# mitosis.net
KiCad netlist of a schematic drawn in Altium Designer
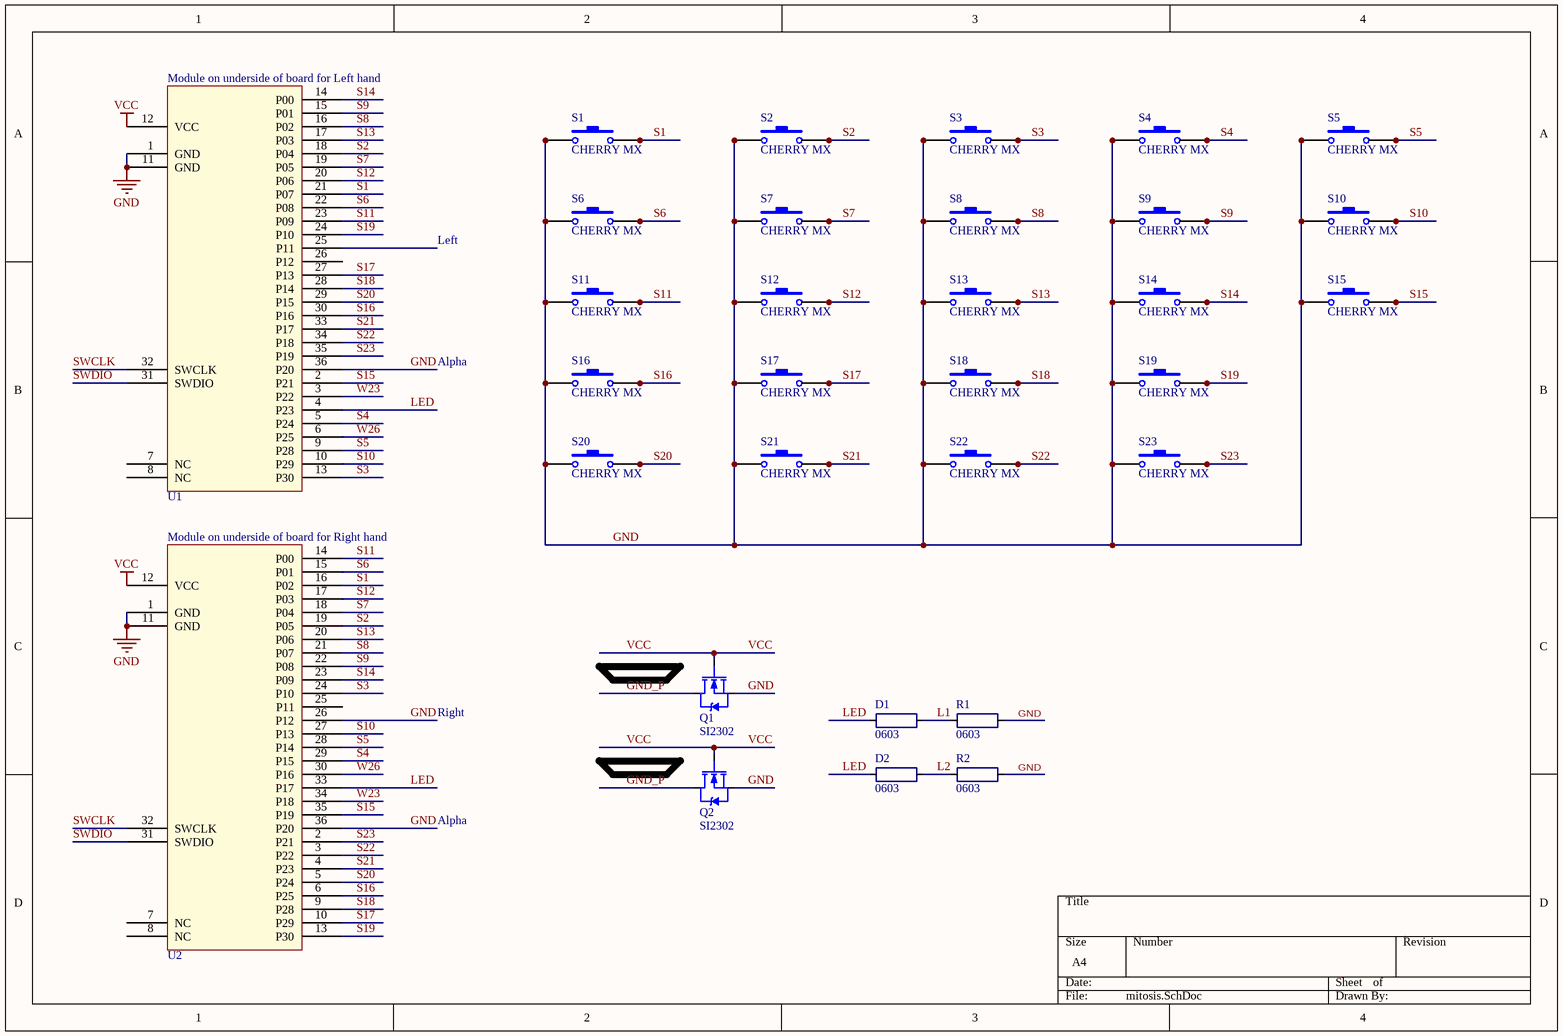
[diagram p0: mitosis.SchDoc]

(export (version "E")
  (design (tool "Eeschema 10.0.6"))
  (components
    (comp (ref "D1") (value "0603") (footprint "RESC2012X06N") (libsource (lib "SK") (part "0603")))
    (comp (ref "D2") (value "0603") (footprint "RESC2012X06N") (libsource (lib "SK") (part "0603")))
    (comp (ref "Q1")
      (value "SI2302")
      (footprint "SOT-23")
      (description "N-Channel Logic MOSFET")
      (fields (field (name "PUBLISHER") "Altium Limited"))
      (libsource (lib "SK") (part "SI2302"))
    )
    (comp (ref "Q2")
      (value "SI2302")
      (footprint "SOT-23")
      (description "N-Channel Logic MOSFET")
      (fields (field (name "PUBLISHER") "Altium Limited"))
      (libsource (lib "SK") (part "SI2302"))
    )
    (comp (ref "R1") (value "0603") (footprint "RESC2012X06N") (libsource (lib "SK") (part "0603")))
    (comp (ref "R2") (value "0603") (footprint "RESC2012X06N") (libsource (lib "SK") (part "0603")))
    (comp (ref "S1")
      (value "CHERRY MX")
      (footprint "cherry")
      (description "Switch")
      (fields (field (name "PUBLISHER") "Altium Limited"))
      (libsource (lib "SK") (part "CHERRY MX"))
    )
    (comp (ref "S2")
      (value "CHERRY MX")
      (footprint "cherry")
      (description "Switch")
      (fields (field (name "PUBLISHER") "Altium Limited"))
      (libsource (lib "SK") (part "CHERRY MX"))
    )
    (comp (ref "S3")
      (value "CHERRY MX")
      (footprint "cherry")
      (description "Switch")
      (fields (field (name "PUBLISHER") "Altium Limited"))
      (libsource (lib "SK") (part "CHERRY MX"))
    )
    (comp (ref "S4")
      (value "CHERRY MX")
      (footprint "cherry")
      (description "Switch")
      (fields (field (name "PUBLISHER") "Altium Limited"))
      (libsource (lib "SK") (part "CHERRY MX"))
    )
    (comp (ref "S5")
      (value "CHERRY MX")
      (footprint "cherry")
      (description "Switch")
      (fields (field (name "PUBLISHER") "Altium Limited"))
      (libsource (lib "SK") (part "CHERRY MX"))
    )
    (comp (ref "S6")
      (value "CHERRY MX")
      (footprint "cherry")
      (description "Switch")
      (fields (field (name "PUBLISHER") "Altium Limited"))
      (libsource (lib "SK") (part "CHERRY MX"))
    )
    (comp (ref "S7")
      (value "CHERRY MX")
      (footprint "cherry")
      (description "Switch")
      (fields (field (name "PUBLISHER") "Altium Limited"))
      (libsource (lib "SK") (part "CHERRY MX"))
    )
    (comp (ref "S8")
      (value "CHERRY MX")
      (footprint "cherry")
      (description "Switch")
      (fields (field (name "PUBLISHER") "Altium Limited"))
      (libsource (lib "SK") (part "CHERRY MX"))
    )
    (comp (ref "S9")
      (value "CHERRY MX")
      (footprint "cherry")
      (description "Switch")
      (fields (field (name "PUBLISHER") "Altium Limited"))
      (libsource (lib "SK") (part "CHERRY MX"))
    )
    (comp (ref "S10")
      (value "CHERRY MX")
      (footprint "cherry")
      (description "Switch")
      (fields (field (name "PUBLISHER") "Altium Limited"))
      (libsource (lib "SK") (part "CHERRY MX"))
    )
    (comp (ref "S11")
      (value "CHERRY MX")
      (footprint "cherry")
      (description "Switch")
      (fields (field (name "PUBLISHER") "Altium Limited"))
      (libsource (lib "SK") (part "CHERRY MX"))
    )
    (comp (ref "S12")
      (value "CHERRY MX")
      (footprint "cherry")
      (description "Switch")
      (fields (field (name "PUBLISHER") "Altium Limited"))
      (libsource (lib "SK") (part "CHERRY MX"))
    )
    (comp (ref "S13")
      (value "CHERRY MX")
      (footprint "cherry")
      (description "Switch")
      (fields (field (name "PUBLISHER") "Altium Limited"))
      (libsource (lib "SK") (part "CHERRY MX"))
    )
    (comp (ref "S14")
      (value "CHERRY MX")
      (footprint "cherry")
      (description "Switch")
      (fields (field (name "PUBLISHER") "Altium Limited"))
      (libsource (lib "SK") (part "CHERRY MX"))
    )
    (comp (ref "S15")
      (value "CHERRY MX")
      (footprint "cherry")
      (description "Switch")
      (fields (field (name "PUBLISHER") "Altium Limited"))
      (libsource (lib "SK") (part "CHERRY MX"))
    )
    (comp (ref "S16")
      (value "CHERRY MX")
      (footprint "cherry")
      (description "Switch")
      (fields (field (name "PUBLISHER") "Altium Limited"))
      (libsource (lib "SK") (part "CHERRY MX"))
    )
    (comp (ref "S17")
      (value "CHERRY MX")
      (footprint "cherry")
      (description "Switch")
      (fields (field (name "PUBLISHER") "Altium Limited"))
      (libsource (lib "SK") (part "CHERRY MX"))
    )
    (comp (ref "S18")
      (value "CHERRY MX")
      (footprint "cherry")
      (description "Switch")
      (fields (field (name "PUBLISHER") "Altium Limited"))
      (libsource (lib "SK") (part "CHERRY MX"))
    )
    (comp (ref "S19")
      (value "CHERRY MX")
      (footprint "cherry")
      (description "Switch")
      (fields (field (name "PUBLISHER") "Altium Limited"))
      (libsource (lib "SK") (part "CHERRY MX"))
    )
    (comp (ref "S20")
      (value "CHERRY MX")
      (footprint "cherry")
      (description "Switch")
      (fields (field (name "PUBLISHER") "Altium Limited"))
      (libsource (lib "SK") (part "CHERRY MX"))
    )
    (comp (ref "S21")
      (value "CHERRY MX")
      (footprint "cherry")
      (description "Switch")
      (fields (field (name "PUBLISHER") "Altium Limited"))
      (libsource (lib "SK") (part "CHERRY MX"))
    )
    (comp (ref "S22")
      (value "CHERRY MX")
      (footprint "cherry")
      (description "Switch")
      (fields (field (name "PUBLISHER") "Altium Limited"))
      (libsource (lib "SK") (part "CHERRY MX"))
    )
    (comp (ref "S23")
      (value "CHERRY MX")
      (footprint "cherry")
      (description "Switch")
      (fields (field (name "PUBLISHER") "Altium Limited"))
      (libsource (lib "SK") (part "CHERRY MX"))
    )
    (comp (ref "U1")
      (value "Core51822 (B)")
      (footprint "Core51822 (B)")
      (description "NRF51822 (B)")
      (libsource (lib "SK") (part "Core51822 (B)"))
    )
    (comp (ref "U2")
      (value "Core51822 (B)")
      (footprint "Core51822 (B)")
      (description "NRF51822 (B)")
      (libsource (lib "SK") (part "Core51822 (B)"))
    )
  )
  (nets
    (net (code "1") (name "/GND_P") (class "Default")
      (node (ref "Q1") (pin "3") (pinfunction "D_3") (pintype "passive"))
      (node (ref "Q2") (pin "3") (pinfunction "D_3") (pintype "passive"))
    )
    (net (code "2") (name "/L1") (class "Default")
      (node (ref "D1") (pin "1") (pinfunction "1_1") (pintype "passive"))
      (node (ref "R1") (pin "2") (pinfunction "2_2") (pintype "passive"))
    )
    (net (code "3") (name "/L2") (class "Default")
      (node (ref "D2") (pin "1") (pinfunction "1_1") (pintype "passive"))
      (node (ref "R2") (pin "2") (pinfunction "2_2") (pintype "passive"))
    )
    (net (code "4") (name "/LED") (class "Default")
      (node (ref "D1") (pin "2") (pinfunction "2_2") (pintype "passive"))
      (node (ref "D2") (pin "2") (pinfunction "2_2") (pintype "passive"))
      (node (ref "U1") (pin "4") (pinfunction "P23_4") (pintype "passive"))
      (node (ref "U2") (pin "33") (pinfunction "P17_33") (pintype "passive"))
    )
    (net (code "5") (name "/S1") (class "Default")
      (node (ref "S1") (pin "10") (pinfunction "10_10") (pintype "passive"))
      (node (ref "S1") (pin "12") (pinfunction "12_12") (pintype "passive"))
      (node (ref "S1") (pin "2") (pinfunction "2_2") (pintype "passive"))
      (node (ref "S1") (pin "4") (pinfunction "4_4") (pintype "passive"))
      (node (ref "S1") (pin "6") (pinfunction "6_6") (pintype "passive"))
      (node (ref "S1") (pin "8") (pinfunction "8_8") (pintype "passive"))
      (node (ref "U1") (pin "21") (pinfunction "P07_21") (pintype "passive"))
      (node (ref "U2") (pin "16") (pinfunction "P02_16") (pintype "passive"))
    )
    (net (code "6") (name "/S2") (class "Default")
      (node (ref "S2") (pin "10") (pinfunction "10_10") (pintype "passive"))
      (node (ref "S2") (pin "12") (pinfunction "12_12") (pintype "passive"))
      (node (ref "S2") (pin "2") (pinfunction "2_2") (pintype "passive"))
      (node (ref "S2") (pin "4") (pinfunction "4_4") (pintype "passive"))
      (node (ref "S2") (pin "6") (pinfunction "6_6") (pintype "passive"))
      (node (ref "S2") (pin "8") (pinfunction "8_8") (pintype "passive"))
      (node (ref "U1") (pin "18") (pinfunction "P04_18") (pintype "passive"))
      (node (ref "U2") (pin "19") (pinfunction "P05_19") (pintype "passive"))
    )
    (net (code "7") (name "/S3") (class "Default")
      (node (ref "S3") (pin "10") (pinfunction "10_10") (pintype "passive"))
      (node (ref "S3") (pin "12") (pinfunction "12_12") (pintype "passive"))
      (node (ref "S3") (pin "2") (pinfunction "2_2") (pintype "passive"))
      (node (ref "S3") (pin "4") (pinfunction "4_4") (pintype "passive"))
      (node (ref "S3") (pin "6") (pinfunction "6_6") (pintype "passive"))
      (node (ref "S3") (pin "8") (pinfunction "8_8") (pintype "passive"))
      (node (ref "U1") (pin "13") (pinfunction "P30_13") (pintype "passive"))
      (node (ref "U2") (pin "24") (pinfunction "P10_24") (pintype "passive"))
    )
    (net (code "8") (name "/S4") (class "Default")
      (node (ref "S4") (pin "10") (pinfunction "10_10") (pintype "passive"))
      (node (ref "S4") (pin "12") (pinfunction "12_12") (pintype "passive"))
      (node (ref "S4") (pin "2") (pinfunction "2_2") (pintype "passive"))
      (node (ref "S4") (pin "4") (pinfunction "4_4") (pintype "passive"))
      (node (ref "S4") (pin "6") (pinfunction "6_6") (pintype "passive"))
      (node (ref "S4") (pin "8") (pinfunction "8_8") (pintype "passive"))
      (node (ref "U1") (pin "5") (pinfunction "P24_5") (pintype "passive"))
      (node (ref "U2") (pin "29") (pinfunction "P15_29") (pintype "passive"))
    )
    (net (code "9") (name "/S5") (class "Default")
      (node (ref "S5") (pin "10") (pinfunction "10_10") (pintype "passive"))
      (node (ref "S5") (pin "12") (pinfunction "12_12") (pintype "passive"))
      (node (ref "S5") (pin "2") (pinfunction "2_2") (pintype "passive"))
      (node (ref "S5") (pin "4") (pinfunction "4_4") (pintype "passive"))
      (node (ref "S5") (pin "6") (pinfunction "6_6") (pintype "passive"))
      (node (ref "S5") (pin "8") (pinfunction "8_8") (pintype "passive"))
      (node (ref "U1") (pin "9") (pinfunction "P28_9") (pintype "passive"))
      (node (ref "U2") (pin "28") (pinfunction "P14_28") (pintype "passive"))
    )
    (net (code "10") (name "/S6") (class "Default")
      (node (ref "S6") (pin "10") (pinfunction "10_10") (pintype "passive"))
      (node (ref "S6") (pin "12") (pinfunction "12_12") (pintype "passive"))
      (node (ref "S6") (pin "2") (pinfunction "2_2") (pintype "passive"))
      (node (ref "S6") (pin "4") (pinfunction "4_4") (pintype "passive"))
      (node (ref "S6") (pin "6") (pinfunction "6_6") (pintype "passive"))
      (node (ref "S6") (pin "8") (pinfunction "8_8") (pintype "passive"))
      (node (ref "U1") (pin "22") (pinfunction "P08_22") (pintype "passive"))
      (node (ref "U2") (pin "15") (pinfunction "P01_15") (pintype "passive"))
    )
    (net (code "11") (name "/S7") (class "Default")
      (node (ref "S7") (pin "10") (pinfunction "10_10") (pintype "passive"))
      (node (ref "S7") (pin "12") (pinfunction "12_12") (pintype "passive"))
      (node (ref "S7") (pin "2") (pinfunction "2_2") (pintype "passive"))
      (node (ref "S7") (pin "4") (pinfunction "4_4") (pintype "passive"))
      (node (ref "S7") (pin "6") (pinfunction "6_6") (pintype "passive"))
      (node (ref "S7") (pin "8") (pinfunction "8_8") (pintype "passive"))
      (node (ref "U1") (pin "19") (pinfunction "P05_19") (pintype "passive"))
      (node (ref "U2") (pin "18") (pinfunction "P04_18") (pintype "passive"))
    )
    (net (code "12") (name "/S8") (class "Default")
      (node (ref "S8") (pin "10") (pinfunction "10_10") (pintype "passive"))
      (node (ref "S8") (pin "12") (pinfunction "12_12") (pintype "passive"))
      (node (ref "S8") (pin "2") (pinfunction "2_2") (pintype "passive"))
      (node (ref "S8") (pin "4") (pinfunction "4_4") (pintype "passive"))
      (node (ref "S8") (pin "6") (pinfunction "6_6") (pintype "passive"))
      (node (ref "S8") (pin "8") (pinfunction "8_8") (pintype "passive"))
      (node (ref "U1") (pin "16") (pinfunction "P02_16") (pintype "passive"))
      (node (ref "U2") (pin "21") (pinfunction "P07_21") (pintype "passive"))
    )
    (net (code "13") (name "/S9") (class "Default")
      (node (ref "S9") (pin "10") (pinfunction "10_10") (pintype "passive"))
      (node (ref "S9") (pin "12") (pinfunction "12_12") (pintype "passive"))
      (node (ref "S9") (pin "2") (pinfunction "2_2") (pintype "passive"))
      (node (ref "S9") (pin "4") (pinfunction "4_4") (pintype "passive"))
      (node (ref "S9") (pin "6") (pinfunction "6_6") (pintype "passive"))
      (node (ref "S9") (pin "8") (pinfunction "8_8") (pintype "passive"))
      (node (ref "U1") (pin "15") (pinfunction "P01_15") (pintype "passive"))
      (node (ref "U2") (pin "22") (pinfunction "P08_22") (pintype "passive"))
    )
    (net (code "14") (name "/S10") (class "Default")
      (node (ref "S10") (pin "10") (pinfunction "10_10") (pintype "passive"))
      (node (ref "S10") (pin "12") (pinfunction "12_12") (pintype "passive"))
      (node (ref "S10") (pin "2") (pinfunction "2_2") (pintype "passive"))
      (node (ref "S10") (pin "4") (pinfunction "4_4") (pintype "passive"))
      (node (ref "S10") (pin "6") (pinfunction "6_6") (pintype "passive"))
      (node (ref "S10") (pin "8") (pinfunction "8_8") (pintype "passive"))
      (node (ref "U1") (pin "10") (pinfunction "P29_10") (pintype "passive"))
      (node (ref "U2") (pin "27") (pinfunction "P13_27") (pintype "passive"))
    )
    (net (code "15") (name "/S11") (class "Default")
      (node (ref "S11") (pin "10") (pinfunction "10_10") (pintype "passive"))
      (node (ref "S11") (pin "12") (pinfunction "12_12") (pintype "passive"))
      (node (ref "S11") (pin "2") (pinfunction "2_2") (pintype "passive"))
      (node (ref "S11") (pin "4") (pinfunction "4_4") (pintype "passive"))
      (node (ref "S11") (pin "6") (pinfunction "6_6") (pintype "passive"))
      (node (ref "S11") (pin "8") (pinfunction "8_8") (pintype "passive"))
      (node (ref "U1") (pin "23") (pinfunction "P09_23") (pintype "passive"))
      (node (ref "U2") (pin "14") (pinfunction "P00_14") (pintype "passive"))
    )
    (net (code "16") (name "/S12") (class "Default")
      (node (ref "S12") (pin "10") (pinfunction "10_10") (pintype "passive"))
      (node (ref "S12") (pin "12") (pinfunction "12_12") (pintype "passive"))
      (node (ref "S12") (pin "2") (pinfunction "2_2") (pintype "passive"))
      (node (ref "S12") (pin "4") (pinfunction "4_4") (pintype "passive"))
      (node (ref "S12") (pin "6") (pinfunction "6_6") (pintype "passive"))
      (node (ref "S12") (pin "8") (pinfunction "8_8") (pintype "passive"))
      (node (ref "U1") (pin "20") (pinfunction "P06_20") (pintype "passive"))
      (node (ref "U2") (pin "17") (pinfunction "P03_17") (pintype "passive"))
    )
    (net (code "17") (name "/S13") (class "Default")
      (node (ref "S13") (pin "10") (pinfunction "10_10") (pintype "passive"))
      (node (ref "S13") (pin "12") (pinfunction "12_12") (pintype "passive"))
      (node (ref "S13") (pin "2") (pinfunction "2_2") (pintype "passive"))
      (node (ref "S13") (pin "4") (pinfunction "4_4") (pintype "passive"))
      (node (ref "S13") (pin "6") (pinfunction "6_6") (pintype "passive"))
      (node (ref "S13") (pin "8") (pinfunction "8_8") (pintype "passive"))
      (node (ref "U1") (pin "17") (pinfunction "P03_17") (pintype "passive"))
      (node (ref "U2") (pin "20") (pinfunction "P06_20") (pintype "passive"))
    )
    (net (code "18") (name "/S14") (class "Default")
      (node (ref "S14") (pin "10") (pinfunction "10_10") (pintype "passive"))
      (node (ref "S14") (pin "12") (pinfunction "12_12") (pintype "passive"))
      (node (ref "S14") (pin "2") (pinfunction "2_2") (pintype "passive"))
      (node (ref "S14") (pin "4") (pinfunction "4_4") (pintype "passive"))
      (node (ref "S14") (pin "6") (pinfunction "6_6") (pintype "passive"))
      (node (ref "S14") (pin "8") (pinfunction "8_8") (pintype "passive"))
      (node (ref "U1") (pin "14") (pinfunction "P00_14") (pintype "passive"))
      (node (ref "U2") (pin "23") (pinfunction "P09_23") (pintype "passive"))
    )
    (net (code "19") (name "/S15") (class "Default")
      (node (ref "S15") (pin "10") (pinfunction "10_10") (pintype "passive"))
      (node (ref "S15") (pin "12") (pinfunction "12_12") (pintype "passive"))
      (node (ref "S15") (pin "2") (pinfunction "2_2") (pintype "passive"))
      (node (ref "S15") (pin "4") (pinfunction "4_4") (pintype "passive"))
      (node (ref "S15") (pin "6") (pinfunction "6_6") (pintype "passive"))
      (node (ref "S15") (pin "8") (pinfunction "8_8") (pintype "passive"))
      (node (ref "U1") (pin "2") (pinfunction "P21_2") (pintype "passive"))
      (node (ref "U2") (pin "35") (pinfunction "P19_35") (pintype "passive"))
    )
    (net (code "20") (name "/S16") (class "Default")
      (node (ref "S16") (pin "10") (pinfunction "10_10") (pintype "passive"))
      (node (ref "S16") (pin "12") (pinfunction "12_12") (pintype "passive"))
      (node (ref "S16") (pin "2") (pinfunction "2_2") (pintype "passive"))
      (node (ref "S16") (pin "4") (pinfunction "4_4") (pintype "passive"))
      (node (ref "S16") (pin "6") (pinfunction "6_6") (pintype "passive"))
      (node (ref "S16") (pin "8") (pinfunction "8_8") (pintype "passive"))
      (node (ref "U1") (pin "30") (pinfunction "P16_30") (pintype "passive"))
      (node (ref "U2") (pin "6") (pinfunction "P25_6") (pintype "passive"))
    )
    (net (code "21") (name "/S17") (class "Default")
      (node (ref "S17") (pin "10") (pinfunction "10_10") (pintype "passive"))
      (node (ref "S17") (pin "12") (pinfunction "12_12") (pintype "passive"))
      (node (ref "S17") (pin "2") (pinfunction "2_2") (pintype "passive"))
      (node (ref "S17") (pin "4") (pinfunction "4_4") (pintype "passive"))
      (node (ref "S17") (pin "6") (pinfunction "6_6") (pintype "passive"))
      (node (ref "S17") (pin "8") (pinfunction "8_8") (pintype "passive"))
      (node (ref "U1") (pin "27") (pinfunction "P13_27") (pintype "passive"))
      (node (ref "U2") (pin "10") (pinfunction "P29_10") (pintype "passive"))
    )
    (net (code "22") (name "/S18") (class "Default")
      (node (ref "S18") (pin "10") (pinfunction "10_10") (pintype "passive"))
      (node (ref "S18") (pin "12") (pinfunction "12_12") (pintype "passive"))
      (node (ref "S18") (pin "2") (pinfunction "2_2") (pintype "passive"))
      (node (ref "S18") (pin "4") (pinfunction "4_4") (pintype "passive"))
      (node (ref "S18") (pin "6") (pinfunction "6_6") (pintype "passive"))
      (node (ref "S18") (pin "8") (pinfunction "8_8") (pintype "passive"))
      (node (ref "U1") (pin "28") (pinfunction "P14_28") (pintype "passive"))
      (node (ref "U2") (pin "9") (pinfunction "P28_9") (pintype "passive"))
    )
    (net (code "23") (name "/S19") (class "Default")
      (node (ref "S19") (pin "10") (pinfunction "10_10") (pintype "passive"))
      (node (ref "S19") (pin "12") (pinfunction "12_12") (pintype "passive"))
      (node (ref "S19") (pin "2") (pinfunction "2_2") (pintype "passive"))
      (node (ref "S19") (pin "4") (pinfunction "4_4") (pintype "passive"))
      (node (ref "S19") (pin "6") (pinfunction "6_6") (pintype "passive"))
      (node (ref "S19") (pin "8") (pinfunction "8_8") (pintype "passive"))
      (node (ref "U1") (pin "24") (pinfunction "P10_24") (pintype "passive"))
      (node (ref "U2") (pin "13") (pinfunction "P30_13") (pintype "passive"))
    )
    (net (code "24") (name "/S20") (class "Default")
      (node (ref "S20") (pin "10") (pinfunction "10_10") (pintype "passive"))
      (node (ref "S20") (pin "12") (pinfunction "12_12") (pintype "passive"))
      (node (ref "S20") (pin "2") (pinfunction "2_2") (pintype "passive"))
      (node (ref "S20") (pin "4") (pinfunction "4_4") (pintype "passive"))
      (node (ref "S20") (pin "6") (pinfunction "6_6") (pintype "passive"))
      (node (ref "S20") (pin "8") (pinfunction "8_8") (pintype "passive"))
      (node (ref "U1") (pin "29") (pinfunction "P15_29") (pintype "passive"))
      (node (ref "U2") (pin "5") (pinfunction "P24_5") (pintype "passive"))
    )
    (net (code "25") (name "/S21") (class "Default")
      (node (ref "S21") (pin "10") (pinfunction "10_10") (pintype "passive"))
      (node (ref "S21") (pin "12") (pinfunction "12_12") (pintype "passive"))
      (node (ref "S21") (pin "2") (pinfunction "2_2") (pintype "passive"))
      (node (ref "S21") (pin "4") (pinfunction "4_4") (pintype "passive"))
      (node (ref "S21") (pin "6") (pinfunction "6_6") (pintype "passive"))
      (node (ref "S21") (pin "8") (pinfunction "8_8") (pintype "passive"))
      (node (ref "U1") (pin "33") (pinfunction "P17_33") (pintype "passive"))
      (node (ref "U2") (pin "4") (pinfunction "P23_4") (pintype "passive"))
    )
    (net (code "26") (name "/S22") (class "Default")
      (node (ref "S22") (pin "10") (pinfunction "10_10") (pintype "passive"))
      (node (ref "S22") (pin "12") (pinfunction "12_12") (pintype "passive"))
      (node (ref "S22") (pin "2") (pinfunction "2_2") (pintype "passive"))
      (node (ref "S22") (pin "4") (pinfunction "4_4") (pintype "passive"))
      (node (ref "S22") (pin "6") (pinfunction "6_6") (pintype "passive"))
      (node (ref "S22") (pin "8") (pinfunction "8_8") (pintype "passive"))
      (node (ref "U1") (pin "34") (pinfunction "P18_34") (pintype "passive"))
      (node (ref "U2") (pin "3") (pinfunction "P22_3") (pintype "passive"))
    )
    (net (code "27") (name "/S23") (class "Default")
      (node (ref "S23") (pin "10") (pinfunction "10_10") (pintype "passive"))
      (node (ref "S23") (pin "12") (pinfunction "12_12") (pintype "passive"))
      (node (ref "S23") (pin "2") (pinfunction "2_2") (pintype "passive"))
      (node (ref "S23") (pin "4") (pinfunction "4_4") (pintype "passive"))
      (node (ref "S23") (pin "6") (pinfunction "6_6") (pintype "passive"))
      (node (ref "S23") (pin "8") (pinfunction "8_8") (pintype "passive"))
      (node (ref "U1") (pin "35") (pinfunction "P19_35") (pintype "passive"))
      (node (ref "U2") (pin "2") (pinfunction "P21_2") (pintype "passive"))
    )
    (net (code "28") (name "/SWCLK") (class "Default")
      (node (ref "U1") (pin "32") (pinfunction "SWCLK_32") (pintype "passive"))
      (node (ref "U2") (pin "32") (pinfunction "SWCLK_32") (pintype "passive"))
    )
    (net (code "29") (name "/SWDIO") (class "Default")
      (node (ref "U1") (pin "31") (pinfunction "SWDIO_31") (pintype "passive"))
      (node (ref "U2") (pin "31") (pinfunction "SWDIO_31") (pintype "passive"))
    )
    (net (code "30") (name "/W23") (class "Default")
      (node (ref "U1") (pin "3") (pinfunction "P22_3") (pintype "passive"))
      (node (ref "U2") (pin "34") (pinfunction "P18_34") (pintype "passive"))
    )
    (net (code "31") (name "/W26") (class "Default")
      (node (ref "U1") (pin "6") (pinfunction "P25_6") (pintype "passive"))
      (node (ref "U2") (pin "30") (pinfunction "P16_30") (pintype "passive"))
    )
    (net (code "32") (name "GND") (class "Default")
      (node (ref "Q1") (pin "2") (pinfunction "S_2") (pintype "passive"))
      (node (ref "Q2") (pin "2") (pinfunction "S_2") (pintype "passive"))
      (node (ref "R1") (pin "1") (pinfunction "1_1") (pintype "passive"))
      (node (ref "R2") (pin "1") (pinfunction "1_1") (pintype "passive"))
      (node (ref "S1") (pin "1") (pinfunction "1_1") (pintype "passive"))
      (node (ref "S1") (pin "11") (pinfunction "11_11") (pintype "passive"))
      (node (ref "S1") (pin "3") (pinfunction "3_3") (pintype "passive"))
      (node (ref "S1") (pin "5") (pinfunction "5_5") (pintype "passive"))
      (node (ref "S1") (pin "7") (pinfunction "7_7") (pintype "passive"))
      (node (ref "S1") (pin "9") (pinfunction "9_9") (pintype "passive"))
      (node (ref "S10") (pin "1") (pinfunction "1_1") (pintype "passive"))
      (node (ref "S10") (pin "11") (pinfunction "11_11") (pintype "passive"))
      (node (ref "S10") (pin "3") (pinfunction "3_3") (pintype "passive"))
      (node (ref "S10") (pin "5") (pinfunction "5_5") (pintype "passive"))
      (node (ref "S10") (pin "7") (pinfunction "7_7") (pintype "passive"))
      (node (ref "S10") (pin "9") (pinfunction "9_9") (pintype "passive"))
      (node (ref "S11") (pin "1") (pinfunction "1_1") (pintype "passive"))
      (node (ref "S11") (pin "11") (pinfunction "11_11") (pintype "passive"))
      (node (ref "S11") (pin "3") (pinfunction "3_3") (pintype "passive"))
      (node (ref "S11") (pin "5") (pinfunction "5_5") (pintype "passive"))
      (node (ref "S11") (pin "7") (pinfunction "7_7") (pintype "passive"))
      (node (ref "S11") (pin "9") (pinfunction "9_9") (pintype "passive"))
      (node (ref "S12") (pin "1") (pinfunction "1_1") (pintype "passive"))
      (node (ref "S12") (pin "11") (pinfunction "11_11") (pintype "passive"))
      (node (ref "S12") (pin "3") (pinfunction "3_3") (pintype "passive"))
      (node (ref "S12") (pin "5") (pinfunction "5_5") (pintype "passive"))
      (node (ref "S12") (pin "7") (pinfunction "7_7") (pintype "passive"))
      (node (ref "S12") (pin "9") (pinfunction "9_9") (pintype "passive"))
      (node (ref "S13") (pin "1") (pinfunction "1_1") (pintype "passive"))
      (node (ref "S13") (pin "11") (pinfunction "11_11") (pintype "passive"))
      (node (ref "S13") (pin "3") (pinfunction "3_3") (pintype "passive"))
      (node (ref "S13") (pin "5") (pinfunction "5_5") (pintype "passive"))
      (node (ref "S13") (pin "7") (pinfunction "7_7") (pintype "passive"))
      (node (ref "S13") (pin "9") (pinfunction "9_9") (pintype "passive"))
      (node (ref "S14") (pin "1") (pinfunction "1_1") (pintype "passive"))
      (node (ref "S14") (pin "11") (pinfunction "11_11") (pintype "passive"))
      (node (ref "S14") (pin "3") (pinfunction "3_3") (pintype "passive"))
      (node (ref "S14") (pin "5") (pinfunction "5_5") (pintype "passive"))
      (node (ref "S14") (pin "7") (pinfunction "7_7") (pintype "passive"))
      (node (ref "S14") (pin "9") (pinfunction "9_9") (pintype "passive"))
      (node (ref "S15") (pin "1") (pinfunction "1_1") (pintype "passive"))
      (node (ref "S15") (pin "11") (pinfunction "11_11") (pintype "passive"))
      (node (ref "S15") (pin "3") (pinfunction "3_3") (pintype "passive"))
      (node (ref "S15") (pin "5") (pinfunction "5_5") (pintype "passive"))
      (node (ref "S15") (pin "7") (pinfunction "7_7") (pintype "passive"))
      (node (ref "S15") (pin "9") (pinfunction "9_9") (pintype "passive"))
      (node (ref "S16") (pin "1") (pinfunction "1_1") (pintype "passive"))
      (node (ref "S16") (pin "11") (pinfunction "11_11") (pintype "passive"))
      (node (ref "S16") (pin "3") (pinfunction "3_3") (pintype "passive"))
      (node (ref "S16") (pin "5") (pinfunction "5_5") (pintype "passive"))
      (node (ref "S16") (pin "7") (pinfunction "7_7") (pintype "passive"))
      (node (ref "S16") (pin "9") (pinfunction "9_9") (pintype "passive"))
      (node (ref "S17") (pin "1") (pinfunction "1_1") (pintype "passive"))
      (node (ref "S17") (pin "11") (pinfunction "11_11") (pintype "passive"))
      (node (ref "S17") (pin "3") (pinfunction "3_3") (pintype "passive"))
      (node (ref "S17") (pin "5") (pinfunction "5_5") (pintype "passive"))
      (node (ref "S17") (pin "7") (pinfunction "7_7") (pintype "passive"))
      (node (ref "S17") (pin "9") (pinfunction "9_9") (pintype "passive"))
      (node (ref "S18") (pin "1") (pinfunction "1_1") (pintype "passive"))
      (node (ref "S18") (pin "11") (pinfunction "11_11") (pintype "passive"))
      (node (ref "S18") (pin "3") (pinfunction "3_3") (pintype "passive"))
      (node (ref "S18") (pin "5") (pinfunction "5_5") (pintype "passive"))
      (node (ref "S18") (pin "7") (pinfunction "7_7") (pintype "passive"))
      (node (ref "S18") (pin "9") (pinfunction "9_9") (pintype "passive"))
      (node (ref "S19") (pin "1") (pinfunction "1_1") (pintype "passive"))
      (node (ref "S19") (pin "11") (pinfunction "11_11") (pintype "passive"))
      (node (ref "S19") (pin "3") (pinfunction "3_3") (pintype "passive"))
      (node (ref "S19") (pin "5") (pinfunction "5_5") (pintype "passive"))
      (node (ref "S19") (pin "7") (pinfunction "7_7") (pintype "passive"))
      (node (ref "S19") (pin "9") (pinfunction "9_9") (pintype "passive"))
      (node (ref "S2") (pin "1") (pinfunction "1_1") (pintype "passive"))
      (node (ref "S2") (pin "11") (pinfunction "11_11") (pintype "passive"))
      (node (ref "S2") (pin "3") (pinfunction "3_3") (pintype "passive"))
      (node (ref "S2") (pin "5") (pinfunction "5_5") (pintype "passive"))
      (node (ref "S2") (pin "7") (pinfunction "7_7") (pintype "passive"))
      (node (ref "S2") (pin "9") (pinfunction "9_9") (pintype "passive"))
      (node (ref "S20") (pin "1") (pinfunction "1_1") (pintype "passive"))
      (node (ref "S20") (pin "11") (pinfunction "11_11") (pintype "passive"))
      (node (ref "S20") (pin "3") (pinfunction "3_3") (pintype "passive"))
      (node (ref "S20") (pin "5") (pinfunction "5_5") (pintype "passive"))
      (node (ref "S20") (pin "7") (pinfunction "7_7") (pintype "passive"))
      (node (ref "S20") (pin "9") (pinfunction "9_9") (pintype "passive"))
      (node (ref "S21") (pin "1") (pinfunction "1_1") (pintype "passive"))
      (node (ref "S21") (pin "11") (pinfunction "11_11") (pintype "passive"))
      (node (ref "S21") (pin "3") (pinfunction "3_3") (pintype "passive"))
      (node (ref "S21") (pin "5") (pinfunction "5_5") (pintype "passive"))
      (node (ref "S21") (pin "7") (pinfunction "7_7") (pintype "passive"))
      (node (ref "S21") (pin "9") (pinfunction "9_9") (pintype "passive"))
      (node (ref "S22") (pin "1") (pinfunction "1_1") (pintype "passive"))
      (node (ref "S22") (pin "11") (pinfunction "11_11") (pintype "passive"))
      (node (ref "S22") (pin "3") (pinfunction "3_3") (pintype "passive"))
      (node (ref "S22") (pin "5") (pinfunction "5_5") (pintype "passive"))
      (node (ref "S22") (pin "7") (pinfunction "7_7") (pintype "passive"))
      (node (ref "S22") (pin "9") (pinfunction "9_9") (pintype "passive"))
      (node (ref "S23") (pin "1") (pinfunction "1_1") (pintype "passive"))
      (node (ref "S23") (pin "11") (pinfunction "11_11") (pintype "passive"))
      (node (ref "S23") (pin "3") (pinfunction "3_3") (pintype "passive"))
      (node (ref "S23") (pin "5") (pinfunction "5_5") (pintype "passive"))
      (node (ref "S23") (pin "7") (pinfunction "7_7") (pintype "passive"))
      (node (ref "S23") (pin "9") (pinfunction "9_9") (pintype "passive"))
      (node (ref "S3") (pin "1") (pinfunction "1_1") (pintype "passive"))
      (node (ref "S3") (pin "11") (pinfunction "11_11") (pintype "passive"))
      (node (ref "S3") (pin "3") (pinfunction "3_3") (pintype "passive"))
      (node (ref "S3") (pin "5") (pinfunction "5_5") (pintype "passive"))
      (node (ref "S3") (pin "7") (pinfunction "7_7") (pintype "passive"))
      (node (ref "S3") (pin "9") (pinfunction "9_9") (pintype "passive"))
      (node (ref "S4") (pin "1") (pinfunction "1_1") (pintype "passive"))
      (node (ref "S4") (pin "11") (pinfunction "11_11") (pintype "passive"))
      (node (ref "S4") (pin "3") (pinfunction "3_3") (pintype "passive"))
      (node (ref "S4") (pin "5") (pinfunction "5_5") (pintype "passive"))
      (node (ref "S4") (pin "7") (pinfunction "7_7") (pintype "passive"))
      (node (ref "S4") (pin "9") (pinfunction "9_9") (pintype "passive"))
      (node (ref "S5") (pin "1") (pinfunction "1_1") (pintype "passive"))
      (node (ref "S5") (pin "11") (pinfunction "11_11") (pintype "passive"))
      (node (ref "S5") (pin "3") (pinfunction "3_3") (pintype "passive"))
      (node (ref "S5") (pin "5") (pinfunction "5_5") (pintype "passive"))
      (node (ref "S5") (pin "7") (pinfunction "7_7") (pintype "passive"))
      (node (ref "S5") (pin "9") (pinfunction "9_9") (pintype "passive"))
      (node (ref "S6") (pin "1") (pinfunction "1_1") (pintype "passive"))
      (node (ref "S6") (pin "11") (pinfunction "11_11") (pintype "passive"))
      (node (ref "S6") (pin "3") (pinfunction "3_3") (pintype "passive"))
      (node (ref "S6") (pin "5") (pinfunction "5_5") (pintype "passive"))
      (node (ref "S6") (pin "7") (pinfunction "7_7") (pintype "passive"))
      (node (ref "S6") (pin "9") (pinfunction "9_9") (pintype "passive"))
      (node (ref "S7") (pin "1") (pinfunction "1_1") (pintype "passive"))
      (node (ref "S7") (pin "11") (pinfunction "11_11") (pintype "passive"))
      (node (ref "S7") (pin "3") (pinfunction "3_3") (pintype "passive"))
      (node (ref "S7") (pin "5") (pinfunction "5_5") (pintype "passive"))
      (node (ref "S7") (pin "7") (pinfunction "7_7") (pintype "passive"))
      (node (ref "S7") (pin "9") (pinfunction "9_9") (pintype "passive"))
      (node (ref "S8") (pin "1") (pinfunction "1_1") (pintype "passive"))
      (node (ref "S8") (pin "11") (pinfunction "11_11") (pintype "passive"))
      (node (ref "S8") (pin "3") (pinfunction "3_3") (pintype "passive"))
      (node (ref "S8") (pin "5") (pinfunction "5_5") (pintype "passive"))
      (node (ref "S8") (pin "7") (pinfunction "7_7") (pintype "passive"))
      (node (ref "S8") (pin "9") (pinfunction "9_9") (pintype "passive"))
      (node (ref "S9") (pin "1") (pinfunction "1_1") (pintype "passive"))
      (node (ref "S9") (pin "11") (pinfunction "11_11") (pintype "passive"))
      (node (ref "S9") (pin "3") (pinfunction "3_3") (pintype "passive"))
      (node (ref "S9") (pin "5") (pinfunction "5_5") (pintype "passive"))
      (node (ref "S9") (pin "7") (pinfunction "7_7") (pintype "passive"))
      (node (ref "S9") (pin "9") (pinfunction "9_9") (pintype "passive"))
      (node (ref "U1") (pin "1") (pinfunction "GND_1") (pintype "passive"))
      (node (ref "U1") (pin "11") (pinfunction "GND_11") (pintype "passive"))
      (node (ref "U1") (pin "36") (pinfunction "P20_36") (pintype "passive"))
      (node (ref "U2") (pin "1") (pinfunction "GND_1") (pintype "passive"))
      (node (ref "U2") (pin "11") (pinfunction "GND_11") (pintype "passive"))
      (node (ref "U2") (pin "26") (pinfunction "P12_26") (pintype "passive"))
      (node (ref "U2") (pin "36") (pinfunction "P20_36") (pintype "passive"))
    )
    (net (code "33") (name "VCC") (class "Default")
      (node (ref "Q1") (pin "1") (pinfunction "G_1") (pintype "passive"))
      (node (ref "Q2") (pin "1") (pinfunction "G_1") (pintype "passive"))
      (node (ref "U1") (pin "12") (pinfunction "VCC_12") (pintype "passive"))
      (node (ref "U2") (pin "12") (pinfunction "VCC_12") (pintype "passive"))
    )
    (net (code "34") (name "unconnected-(U1-NC-Pad7)") (class "Default")
      (node (ref "U1") (pin "7") (pinfunction "NC_7") (pintype "passive"))
    )
    (net (code "35") (name "unconnected-(U1-NC-Pad8)") (class "Default")
      (node (ref "U1") (pin "8") (pinfunction "NC_8") (pintype "passive"))
    )
    (net (code "36") (name "unconnected-(U1-P11-Pad25)") (class "Default")
      (node (ref "U1") (pin "25") (pinfunction "P11_25") (pintype "passive"))
    )
    (net (code "37") (name "unconnected-(U1-P12-Pad26)") (class "Default")
      (node (ref "U1") (pin "26") (pinfunction "P12_26") (pintype "passive"))
    )
    (net (code "38") (name "unconnected-(U2-NC-Pad7)") (class "Default")
      (node (ref "U2") (pin "7") (pinfunction "NC_7") (pintype "passive"))
    )
    (net (code "39") (name "unconnected-(U2-NC-Pad8)") (class "Default")
      (node (ref "U2") (pin "8") (pinfunction "NC_8") (pintype "passive"))
    )
    (net (code "40") (name "unconnected-(U2-P11-Pad25)") (class "Default")
      (node (ref "U2") (pin "25") (pinfunction "P11_25") (pintype "passive"))
    )
  )
)
